# SmartLamp_2020-11-09_21-14-12.net
KiCad netlist of a schematic drawn in EasyEDA
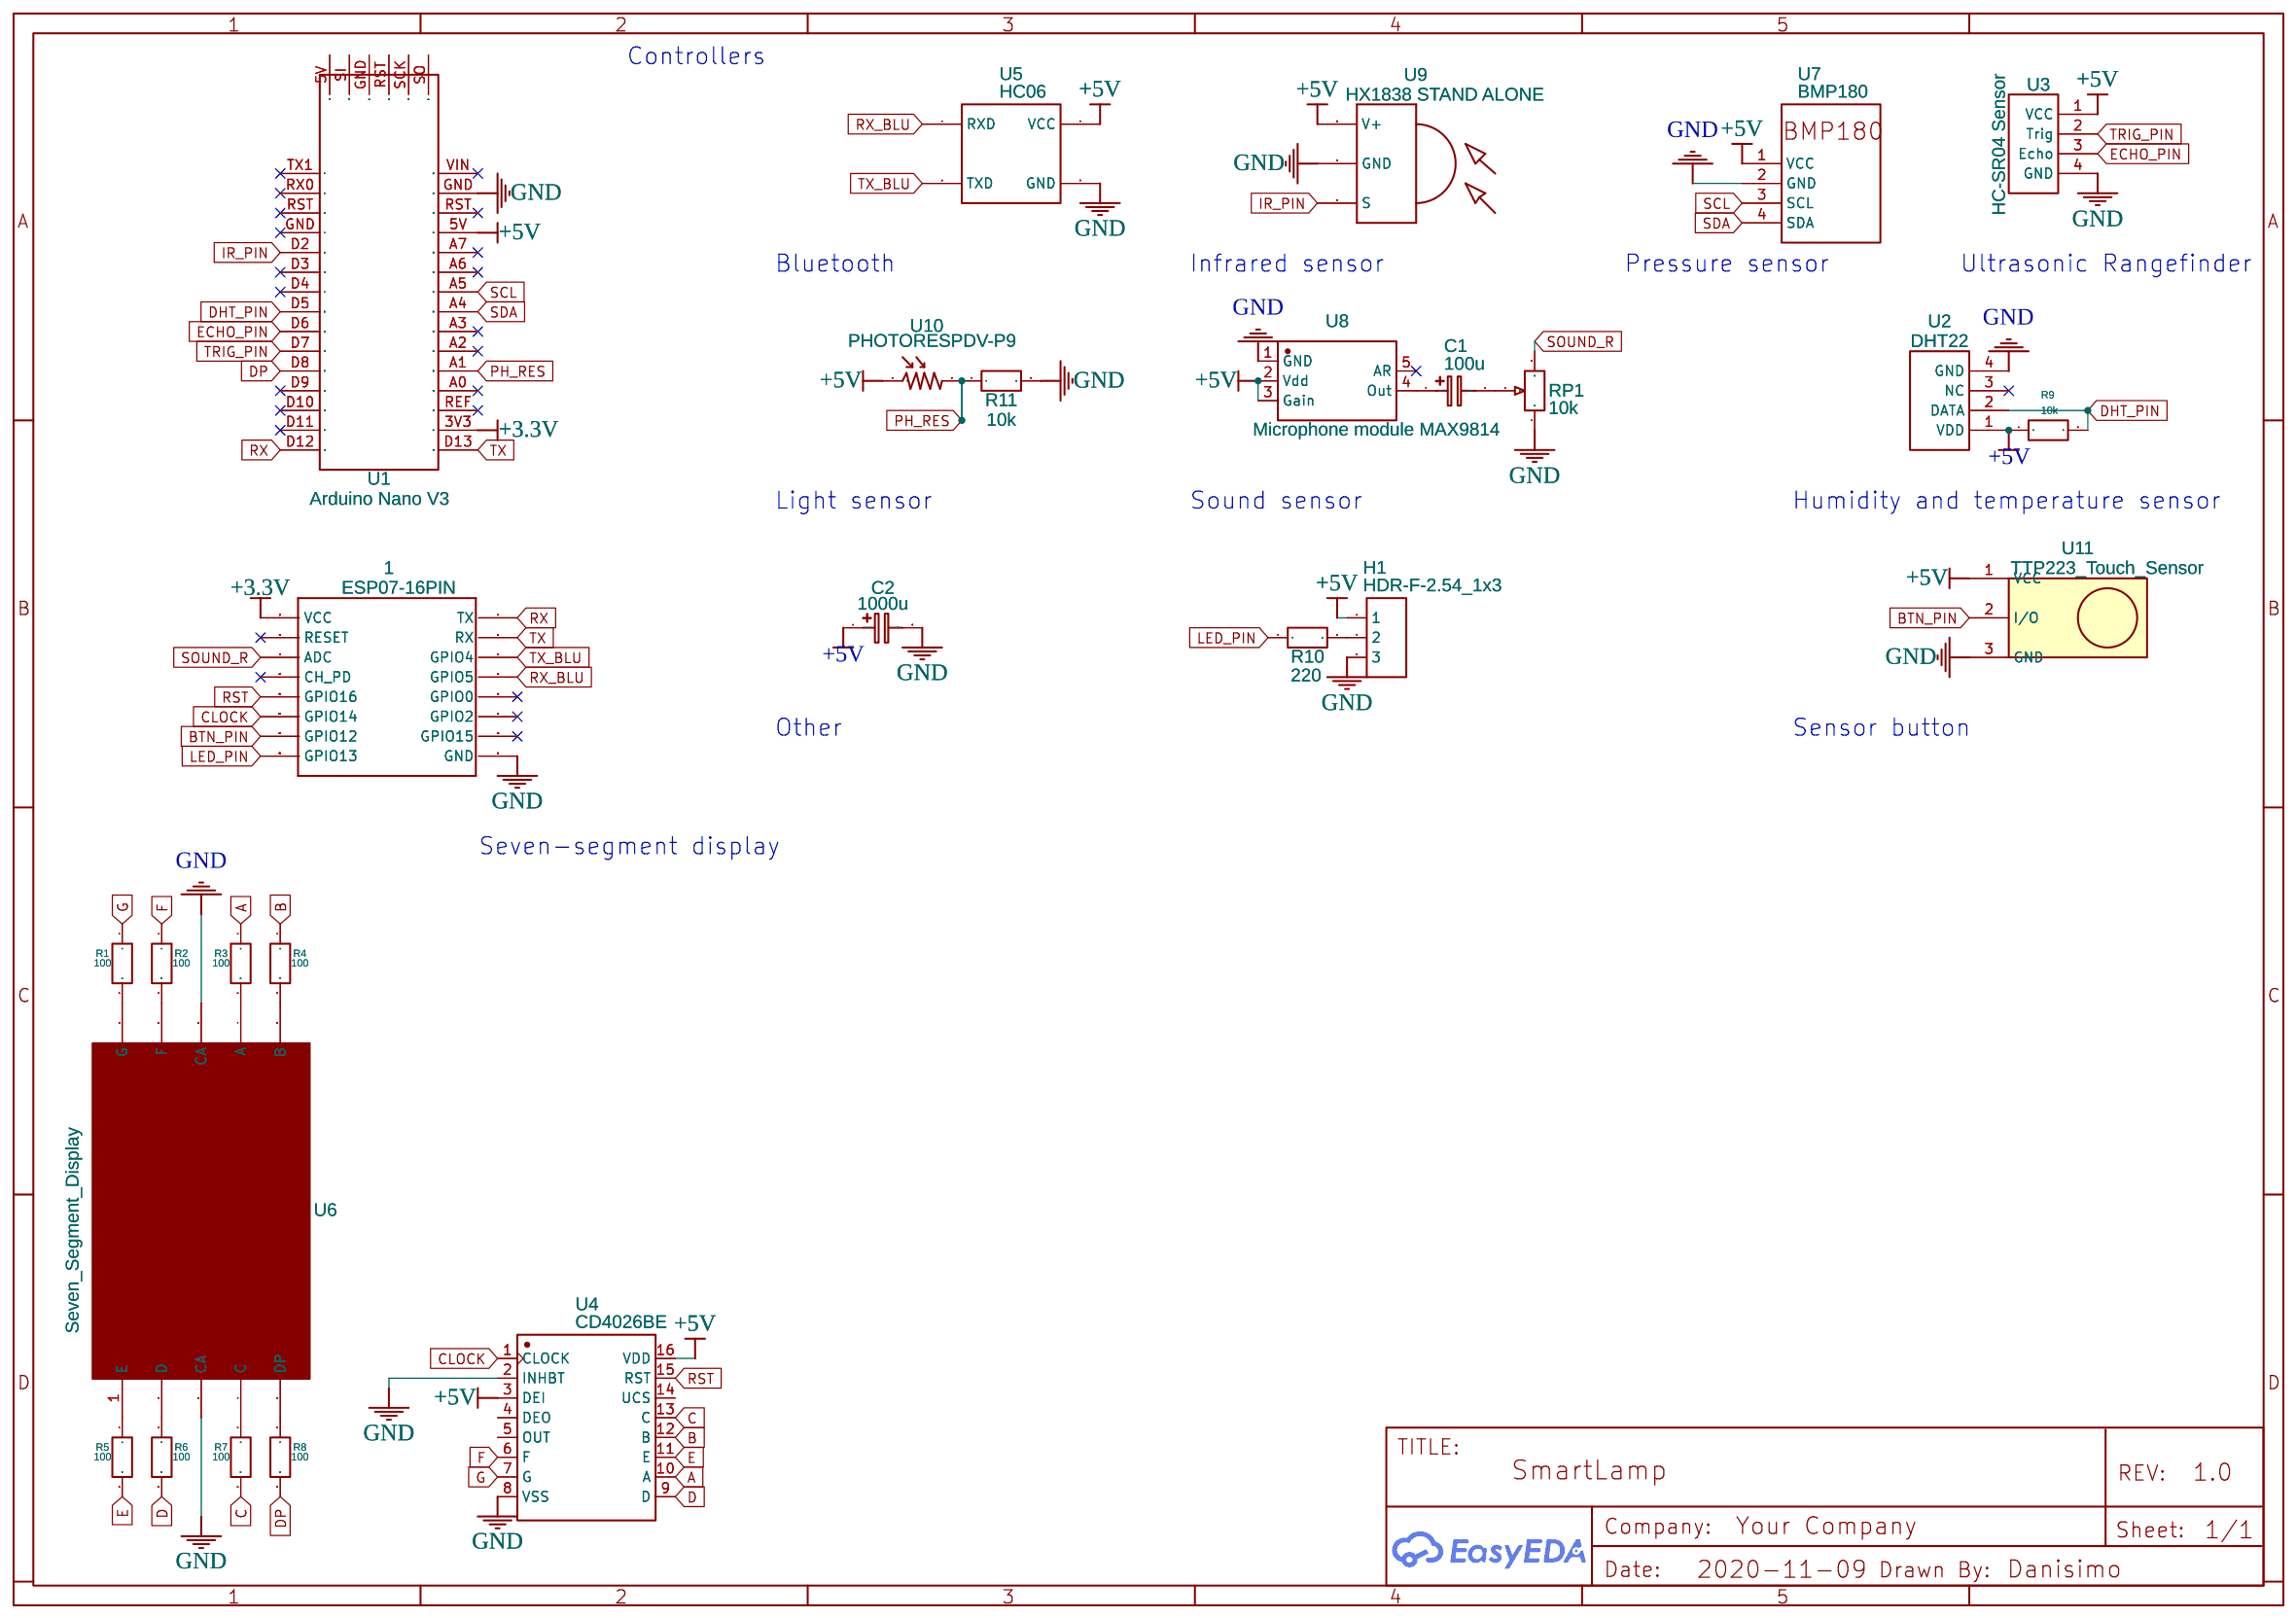
[diagram p0: schematic sheet]

(export (version "E")
  (design (tool "Eeschema 10.0.6"))
  (components
    (comp (ref "1") (value "ESP07-16PIN") (libsource (lib "") (part "ESP07-16PIN")))
    (comp (ref "C1") (value "100u") (libsource (lib "") (part "C_Tan_SMD_A_EU_1")))
    (comp (ref "C2") (value "1000u") (libsource (lib "") (part "C_Tan_SMD_A_EU")))
    (comp (ref "H1")
      (value "HDR-F-2.54_1x3")
      (fields (field (name "BOM_Supplier Part") "C146690"))
      (libsource (lib "") (part "HDR-F-2.54_1x3"))
    )
    (comp (ref "R1") (value "100") (libsource (lib "") (part "R_0603_EU")))
    (comp (ref "R2") (value "100") (libsource (lib "") (part "R_0603_EU")))
    (comp (ref "R3") (value "100") (libsource (lib "") (part "R_0603_EU")))
    (comp (ref "R4") (value "100") (libsource (lib "") (part "R_0603_EU")))
    (comp (ref "R5") (value "100") (libsource (lib "") (part "R_0603_EU")))
    (comp (ref "R6") (value "100") (libsource (lib "") (part "R_0603_EU")))
    (comp (ref "R7") (value "100") (libsource (lib "") (part "R_0603_EU")))
    (comp (ref "R8") (value "100") (libsource (lib "") (part "R_0603_EU")))
    (comp (ref "R9") (value "10k") (libsource (lib "") (part "R_0603_EU_1")))
    (comp (ref "R10") (value "220") (libsource (lib "") (part "R_0603_EU_1")))
    (comp (ref "R11") (value "10k") (libsource (lib "") (part "R_0603_EU_1")))
    (comp (ref "RP1") (value "10k") (libsource (lib "") (part "R_3386P_EU")))
    (comp (ref "U1") (value "Arduino Nano V3") (libsource (lib "") (part "Arduino Nano V3")))
    (comp (ref "U2") (value "DHT22") (libsource (lib "") (part "DHT22")))
    (comp (ref "U3")
      (value "HC-SR04 Sensor")
      (fields (field (name "BOM_Manufacturer Part") "Pin_Header_4P"))
      (libsource (lib "") (part "My HC-SR04 Sensor"))
    )
    (comp (ref "U4")
      (value "CD4026BE")
      (fields (field (name "BOM_Supplier Part") "C89909"))
      (libsource (lib "") (part "CD4026BE"))
    )
    (comp (ref "U5") (value "HC06") (libsource (lib "") (part "HC06")))
    (comp (ref "U6") (value "Seven_Segment_Display") (libsource (lib "") (part "Seven_Segment_Display")))
    (comp (ref "U7") (value "BMP180") (libsource (lib "") (part "BMP180_NICKS")))
    (comp (ref "U8")
      (value "Microphone module MAX9814")
      (libsource (lib "") (part "Microphone module MAX9814"))
    )
    (comp (ref "U9") (value "HX1838 STAND ALONE") (libsource (lib "") (part "HX1838 STAND ALONE")))
    (comp (ref "U10") (value "PHOTORESPDV-P9") (libsource (lib "") (part "PHOTORESPDV-P9")))
    (comp (ref "U11")
      (value "TTP223_Touch_Sensor")
      (fields (field (name "BOM_Manufacturer Part") "TTP223 BREAKOUT"))
      (libsource (lib "") (part "TTP223_Touch_Sensor"))
    )
  )
  (nets
    (net (code "1") (name "+3.3V") (class "Default")
      (node (ref "1") (pin "VCC") (pinfunction "VCC_VCC") (pintype "bidirectional"))
      (node (ref "U1") (pin "3V3") (pinfunction "17_3V3") (pintype "unspecified"))
    )
    (net (code "2") (name "+5V") (class "Default")
      (node (ref "C2") (pin "1") (pinfunction "1_1") (pintype "unspecified"))
      (node (ref "H1") (pin "1") (pinfunction "1_1") (pintype "input"))
      (node (ref "R9") (pin "1") (pinfunction "1_1") (pintype "unspecified"))
      (node (ref "U1") (pin "5V") (pinfunction "27_5V") (pintype "unspecified"))
      (node (ref "U10") (pin "1") (pinfunction "1_1") (pintype "unspecified"))
      (node (ref "U11") (pin "1") (pinfunction "VCC_1") (pintype "unspecified"))
      (node (ref "U2") (pin "1") (pinfunction "VDD_1") (pintype "unspecified"))
      (node (ref "U3") (pin "1") (pinfunction "VCC_1") (pintype "unspecified"))
      (node (ref "U4") (pin "16") (pinfunction "VDD_16") (pintype "unspecified"))
      (node (ref "U4") (pin "3") (pinfunction "DEI_3") (pintype "unspecified"))
      (node (ref "U5") (pin "1") (pinfunction "VCC_1") (pintype "unspecified"))
      (node (ref "U7") (pin "1") (pinfunction "VCC_1") (pintype "unspecified"))
      (node (ref "U8") (pin "2") (pinfunction "Vdd_2") (pintype "unspecified"))
      (node (ref "U8") (pin "3") (pinfunction "Gain_3") (pintype "unspecified"))
      (node (ref "U9") (pin "VCC") (pinfunction "V+_VCC") (pintype "unspecified"))
    )
    (net (code "3") (name "A") (class "Default")
      (node (ref "R3") (pin "1") (pinfunction "1_1") (pintype "unspecified"))
      (node (ref "U4") (pin "10") (pinfunction "A_10") (pintype "unspecified"))
    )
    (net (code "4") (name "B") (class "Default")
      (node (ref "R4") (pin "1") (pinfunction "1_1") (pintype "unspecified"))
      (node (ref "U4") (pin "12") (pinfunction "B_12") (pintype "unspecified"))
    )
    (net (code "5") (name "BTN_PIN") (class "Default")
      (node (ref "1") (pin "GPIO12") (pinfunction "GPIO12_GPIO12") (pintype "bidirectional"))
      (node (ref "U11") (pin "2") (pinfunction "I/O_2") (pintype "unspecified"))
    )
    (net (code "6") (name "C") (class "Default")
      (node (ref "R7") (pin "2") (pinfunction "2_2") (pintype "unspecified"))
      (node (ref "U4") (pin "13") (pinfunction "C_13") (pintype "unspecified"))
    )
    (net (code "7") (name "CLOCK") (class "Default")
      (node (ref "1") (pin "GPIO14") (pinfunction "GPIO14_GPIO14") (pintype "bidirectional"))
      (node (ref "U4") (pin "1") (pinfunction "CLOCK_1") (pintype "unspecified"))
    )
    (net (code "8") (name "D") (class "Default")
      (node (ref "R6") (pin "2") (pinfunction "2_2") (pintype "unspecified"))
      (node (ref "U4") (pin "9") (pinfunction "D_9") (pintype "unspecified"))
    )
    (net (code "9") (name "DHT_PIN") (class "Default")
      (node (ref "R9") (pin "2") (pinfunction "2_2") (pintype "unspecified"))
      (node (ref "U1") (pin "D5") (pinfunction "8_D5") (pintype "unspecified"))
      (node (ref "U2") (pin "2") (pinfunction "DATA_2") (pintype "unspecified"))
    )
    (net (code "10") (name "DP") (class "Default")
      (node (ref "R8") (pin "2") (pinfunction "2_2") (pintype "unspecified"))
      (node (ref "U1") (pin "D8") (pinfunction "11_D8") (pintype "unspecified"))
    )
    (net (code "11") (name "E") (class "Default")
      (node (ref "R5") (pin "2") (pinfunction "2_2") (pintype "unspecified"))
      (node (ref "U4") (pin "11") (pinfunction "E_11") (pintype "unspecified"))
    )
    (net (code "12") (name "ECHO_PIN") (class "Default")
      (node (ref "U1") (pin "D6") (pinfunction "9_D6") (pintype "unspecified"))
      (node (ref "U3") (pin "3") (pinfunction "Echo_3") (pintype "unspecified"))
    )
    (net (code "13") (name "F") (class "Default")
      (node (ref "R2") (pin "1") (pinfunction "1_1") (pintype "unspecified"))
      (node (ref "U4") (pin "6") (pinfunction "F_6") (pintype "unspecified"))
    )
    (net (code "14") (name "G") (class "Default")
      (node (ref "R1") (pin "1") (pinfunction "1_1") (pintype "unspecified"))
      (node (ref "U4") (pin "7") (pinfunction "G_7") (pintype "unspecified"))
    )
    (net (code "15") (name "GND") (class "Default")
      (node (ref "1") (pin "GND") (pinfunction "GND_GND") (pintype "bidirectional"))
      (node (ref "C2") (pin "2") (pinfunction "2_2") (pintype "unspecified"))
      (node (ref "H1") (pin "3") (pinfunction "3_3") (pintype "input"))
      (node (ref "R11") (pin "2") (pinfunction "2_2") (pintype "unspecified"))
      (node (ref "RP1") (pin "1") (pinfunction "1_1") (pintype "input"))
      (node (ref "U1") (pin "GND") (pinfunction "29_GND") (pintype "unspecified"))
      (node (ref "U11") (pin "3") (pinfunction "GND_3") (pintype "unspecified"))
      (node (ref "U2") (pin "4") (pinfunction "GND_4") (pintype "unspecified"))
      (node (ref "U3") (pin "4") (pinfunction "GND_4") (pintype "unspecified"))
      (node (ref "U4") (pin "2") (pinfunction "INHBT_2") (pintype "unspecified"))
      (node (ref "U4") (pin "8") (pinfunction "VSS_8") (pintype "unspecified"))
      (node (ref "U5") (pin "2") (pinfunction "GND_2") (pintype "unspecified"))
      (node (ref "U6") (pin "3") (pinfunction "CA_3") (pintype "unspecified"))
      (node (ref "U6") (pin "8") (pinfunction "CA_8") (pintype "unspecified"))
      (node (ref "U7") (pin "2") (pinfunction "GND_2") (pintype "unspecified"))
      (node (ref "U8") (pin "1") (pinfunction "GND_1") (pintype "unspecified"))
      (node (ref "U9") (pin "GND") (pinfunction "GND_GND") (pintype "unspecified"))
    )
    (net (code "16") (name "IR_PIN") (class "Default")
      (node (ref "U1") (pin "D2") (pinfunction "5_D2") (pintype "unspecified"))
      (node (ref "U9") (pin "S") (pinfunction "S_S") (pintype "unspecified"))
    )
    (net (code "17") (name "LED_PIN") (class "Default")
      (node (ref "1") (pin "GPIO13") (pinfunction "GPIO13_GPIO13") (pintype "bidirectional"))
      (node (ref "R10") (pin "1") (pinfunction "1_1") (pintype "unspecified"))
    )
    (net (code "18") (name "Net-(C1-Pad2)") (class "Default")
      (node (ref "C1") (pin "2") (pinfunction "2_2") (pintype "unspecified"))
      (node (ref "RP1") (pin "2") (pinfunction "2_2") (pintype "input"))
    )
    (net (code "19") (name "Net-(H1-Pad2)") (class "Default")
      (node (ref "H1") (pin "2") (pinfunction "2_2") (pintype "input"))
      (node (ref "R10") (pin "2") (pinfunction "2_2") (pintype "unspecified"))
    )
    (net (code "20") (name "Net-(U6-A)") (class "Default")
      (node (ref "R3") (pin "2") (pinfunction "2_2") (pintype "unspecified"))
      (node (ref "U6") (pin "7") (pinfunction "A_7") (pintype "unspecified"))
    )
    (net (code "21") (name "Net-(U6-B)") (class "Default")
      (node (ref "R4") (pin "2") (pinfunction "2_2") (pintype "unspecified"))
      (node (ref "U6") (pin "6") (pinfunction "B_6") (pintype "unspecified"))
    )
    (net (code "22") (name "Net-(U6-C)") (class "Default")
      (node (ref "R7") (pin "1") (pinfunction "1_1") (pintype "unspecified"))
      (node (ref "U6") (pin "4") (pinfunction "C_4") (pintype "unspecified"))
    )
    (net (code "23") (name "Net-(U6-D)") (class "Default")
      (node (ref "R6") (pin "1") (pinfunction "1_1") (pintype "unspecified"))
      (node (ref "U6") (pin "2") (pinfunction "D_2") (pintype "unspecified"))
    )
    (net (code "24") (name "Net-(U6-DP)") (class "Default")
      (node (ref "R8") (pin "1") (pinfunction "1_1") (pintype "unspecified"))
      (node (ref "U6") (pin "5") (pinfunction "DP_5") (pintype "unspecified"))
    )
    (net (code "25") (name "Net-(U6-E)") (class "Default")
      (node (ref "R5") (pin "1") (pinfunction "1_1") (pintype "unspecified"))
      (node (ref "U6") (pin "1") (pinfunction "E_1") (pintype "unspecified"))
    )
    (net (code "26") (name "Net-(U6-F)") (class "Default")
      (node (ref "R2") (pin "2") (pinfunction "2_2") (pintype "unspecified"))
      (node (ref "U6") (pin "9") (pinfunction "F_9") (pintype "unspecified"))
    )
    (net (code "27") (name "Net-(U6-G)") (class "Default")
      (node (ref "R1") (pin "2") (pinfunction "2_2") (pintype "unspecified"))
      (node (ref "U6") (pin "10") (pinfunction "G_10") (pintype "unspecified"))
    )
    (net (code "28") (name "Net-(U8-Out)") (class "Default")
      (node (ref "C1") (pin "1") (pinfunction "1_1") (pintype "unspecified"))
      (node (ref "U8") (pin "4") (pinfunction "Out_4") (pintype "unspecified"))
    )
    (net (code "29") (name "PH_RES") (class "Default")
      (node (ref "R11") (pin "1") (pinfunction "1_1") (pintype "unspecified"))
      (node (ref "U1") (pin "A1") (pinfunction "20_A1") (pintype "unspecified"))
      (node (ref "U10") (pin "2") (pinfunction "2_2") (pintype "unspecified"))
    )
    (net (code "30") (name "RST") (class "Default")
      (node (ref "1") (pin "GPIO16") (pinfunction "GPIO16_GPIO16") (pintype "bidirectional"))
      (node (ref "U4") (pin "15") (pinfunction "RST_15") (pintype "unspecified"))
    )
    (net (code "31") (name "RX") (class "Default")
      (node (ref "1") (pin "TX") (pinfunction "TX_TX") (pintype "bidirectional"))
      (node (ref "U1") (pin "D12") (pinfunction "15_D12") (pintype "unspecified"))
    )
    (net (code "32") (name "RX_BLU") (class "Default")
      (node (ref "1") (pin "GPIO5") (pinfunction "GPIO5_GPIO5") (pintype "bidirectional"))
      (node (ref "U5") (pin "4") (pinfunction "RXD_4") (pintype "unspecified"))
    )
    (net (code "33") (name "SCL") (class "Default")
      (node (ref "U1") (pin "A5") (pinfunction "24_A5") (pintype "unspecified"))
      (node (ref "U7") (pin "3") (pinfunction "SCL_3") (pintype "unspecified"))
    )
    (net (code "34") (name "SDA") (class "Default")
      (node (ref "U1") (pin "A4") (pinfunction "23_A4") (pintype "unspecified"))
      (node (ref "U7") (pin "4") (pinfunction "SDA_4") (pintype "unspecified"))
    )
    (net (code "35") (name "SOUND_R") (class "Default")
      (node (ref "1") (pin "ADC") (pinfunction "ADC_ADC") (pintype "bidirectional"))
      (node (ref "RP1") (pin "3") (pinfunction "3_3") (pintype "input"))
    )
    (net (code "36") (name "TRIG_PIN") (class "Default")
      (node (ref "U1") (pin "D7") (pinfunction "D7_D7") (pintype "unspecified"))
      (node (ref "U3") (pin "2") (pinfunction "Trig_2") (pintype "unspecified"))
    )
    (net (code "37") (name "TX") (class "Default")
      (node (ref "1") (pin "RX") (pinfunction "RX_RX") (pintype "bidirectional"))
      (node (ref "U1") (pin "D13") (pinfunction "16_D13") (pintype "unspecified"))
    )
    (net (code "38") (name "TX_BLU") (class "Default")
      (node (ref "1") (pin "GPIO4") (pinfunction "GPIO4_GPIO4") (pintype "bidirectional"))
      (node (ref "U5") (pin "3") (pinfunction "TXD_3") (pintype "unspecified"))
    )
    (net (code "39") (name "unconnected-(1-PadCH_PD)") (class "Default")
      (node (ref "1") (pin "CH_PD") (pinfunction "CH_PD_CH_PD") (pintype "bidirectional+no_connect"))
    )
    (net (code "40") (name "unconnected-(1-PadGPIO0)") (class "Default")
      (node (ref "1") (pin "GPIO0") (pinfunction "GPIO0_GPIO0") (pintype "bidirectional+no_connect"))
    )
    (net (code "41") (name "unconnected-(1-PadGPIO2)") (class "Default")
      (node (ref "1") (pin "GPIO2") (pinfunction "GPIO2_GPIO2") (pintype "bidirectional+no_connect"))
    )
    (net (code "42") (name "unconnected-(1-PadGPIO15)") (class "Default")
      (node (ref "1") (pin "GPIO15") (pinfunction "GPIO15_GPIO15") (pintype "bidirectional+no_connect"))
    )
    (net (code "43") (name "unconnected-(1-RESET-PadREST)") (class "Default")
      (node (ref "1") (pin "REST") (pinfunction "RESET_REST") (pintype "bidirectional+no_connect"))
    )
    (net (code "44") (name "unconnected-(U1-1-PadTX1)") (class "Default")
      (node (ref "U1") (pin "TX1") (pinfunction "1_TX1") (pintype "unspecified+no_connect"))
    )
    (net (code "45") (name "unconnected-(U1-2-PadRX0)") (class "Default")
      (node (ref "U1") (pin "RX0") (pinfunction "2_RX0") (pintype "unspecified+no_connect"))
    )
    (net (code "46") (name "unconnected-(U1-3-PadRST)") (class "Default")
      (node (ref "U1") (pin "RST") (pinfunction "3_RST") (pintype "unspecified+no_connect"))
    )
    (net (code "47") (name "unconnected-(U1-4-PadGND)") (class "Default")
      (node (ref "U1") (pin "GND") (pinfunction "4_GND") (pintype "unspecified+no_connect"))
    )
    (net (code "48") (name "unconnected-(U1-6-PadD3)") (class "Default")
      (node (ref "U1") (pin "D3") (pinfunction "6_D3") (pintype "unspecified+no_connect"))
    )
    (net (code "49") (name "unconnected-(U1-7-PadD4)") (class "Default")
      (node (ref "U1") (pin "D4") (pinfunction "7_D4") (pintype "unspecified+no_connect"))
    )
    (net (code "50") (name "unconnected-(U1-12-PadD9)") (class "Default")
      (node (ref "U1") (pin "D9") (pinfunction "12_D9") (pintype "unspecified+no_connect"))
    )
    (net (code "51") (name "unconnected-(U1-13-PadD10)") (class "Default")
      (node (ref "U1") (pin "D10") (pinfunction "13_D10") (pintype "unspecified+no_connect"))
    )
    (net (code "52") (name "unconnected-(U1-14-PadD11)") (class "Default")
      (node (ref "U1") (pin "D11") (pinfunction "14_D11") (pintype "unspecified+no_connect"))
    )
    (net (code "53") (name "unconnected-(U1-18-PadREF)") (class "Default")
      (node (ref "U1") (pin "REF") (pinfunction "18_REF") (pintype "unspecified+no_connect"))
    )
    (net (code "54") (name "unconnected-(U1-19-PadA0)") (class "Default")
      (node (ref "U1") (pin "A0") (pinfunction "19_A0") (pintype "unspecified+no_connect"))
    )
    (net (code "55") (name "unconnected-(U1-21-PadA2)") (class "Default")
      (node (ref "U1") (pin "A2") (pinfunction "21_A2") (pintype "unspecified+no_connect"))
    )
    (net (code "56") (name "unconnected-(U1-22-PadA3)") (class "Default")
      (node (ref "U1") (pin "A3") (pinfunction "22_A3") (pintype "unspecified+no_connect"))
    )
    (net (code "57") (name "unconnected-(U1-25-PadA6)") (class "Default")
      (node (ref "U1") (pin "A6") (pinfunction "25_A6") (pintype "unspecified+no_connect"))
    )
    (net (code "58") (name "unconnected-(U1-26-PadA7)") (class "Default")
      (node (ref "U1") (pin "A7") (pinfunction "26_A7") (pintype "unspecified+no_connect"))
    )
    (net (code "59") (name "unconnected-(U1-28-PadRST)") (class "Default")
      (node (ref "U1") (pin "RST") (pinfunction "28_RST") (pintype "unspecified+no_connect"))
    )
    (net (code "60") (name "unconnected-(U1-30-PadVIN)") (class "Default")
      (node (ref "U1") (pin "VIN") (pinfunction "30_VIN") (pintype "unspecified+no_connect"))
    )
    (net (code "61") (name "unconnected-(U1-31-PadSO)") (class "Default")
      (node (ref "U1") (pin "SO") (pinfunction "31_SO") (pintype "unspecified"))
    )
    (net (code "62") (name "unconnected-(U1-32-PadSCK)") (class "Default")
      (node (ref "U1") (pin "SCK") (pinfunction "32_SCK") (pintype "unspecified"))
    )
    (net (code "63") (name "unconnected-(U1-33-PadRST)") (class "Default")
      (node (ref "U1") (pin "RST") (pinfunction "33_RST") (pintype "unspecified"))
    )
    (net (code "64") (name "unconnected-(U1-34-PadGND)") (class "Default")
      (node (ref "U1") (pin "GND") (pinfunction "34_GND") (pintype "unspecified"))
    )
    (net (code "65") (name "unconnected-(U1-35-PadSI)") (class "Default")
      (node (ref "U1") (pin "SI") (pinfunction "35_SI") (pintype "unspecified"))
    )
    (net (code "66") (name "unconnected-(U1-36-Pad5V)") (class "Default")
      (node (ref "U1") (pin "5V") (pinfunction "36_5V") (pintype "unspecified"))
    )
    (net (code "67") (name "unconnected-(U2-NC-Pad3)") (class "Default")
      (node (ref "U2") (pin "3") (pinfunction "NC_3") (pintype "unspecified+no_connect"))
    )
    (net (code "68") (name "unconnected-(U4-DEO-Pad4)") (class "Default")
      (node (ref "U4") (pin "4") (pinfunction "DEO_4") (pintype "unspecified"))
    )
    (net (code "69") (name "unconnected-(U4-OUT-Pad5)") (class "Default")
      (node (ref "U4") (pin "5") (pinfunction "OUT_5") (pintype "unspecified"))
    )
    (net (code "70") (name "unconnected-(U4-UCS-Pad14)") (class "Default")
      (node (ref "U4") (pin "14") (pinfunction "UCS_14") (pintype "unspecified"))
    )
    (net (code "71") (name "unconnected-(U8-AR-Pad5)") (class "Default")
      (node (ref "U8") (pin "5") (pinfunction "AR_5") (pintype "unspecified+no_connect"))
    )
  )
)
